# T01_Synth_Glove_v4.net
KiCad netlist of a schematic drawn in EAGLE
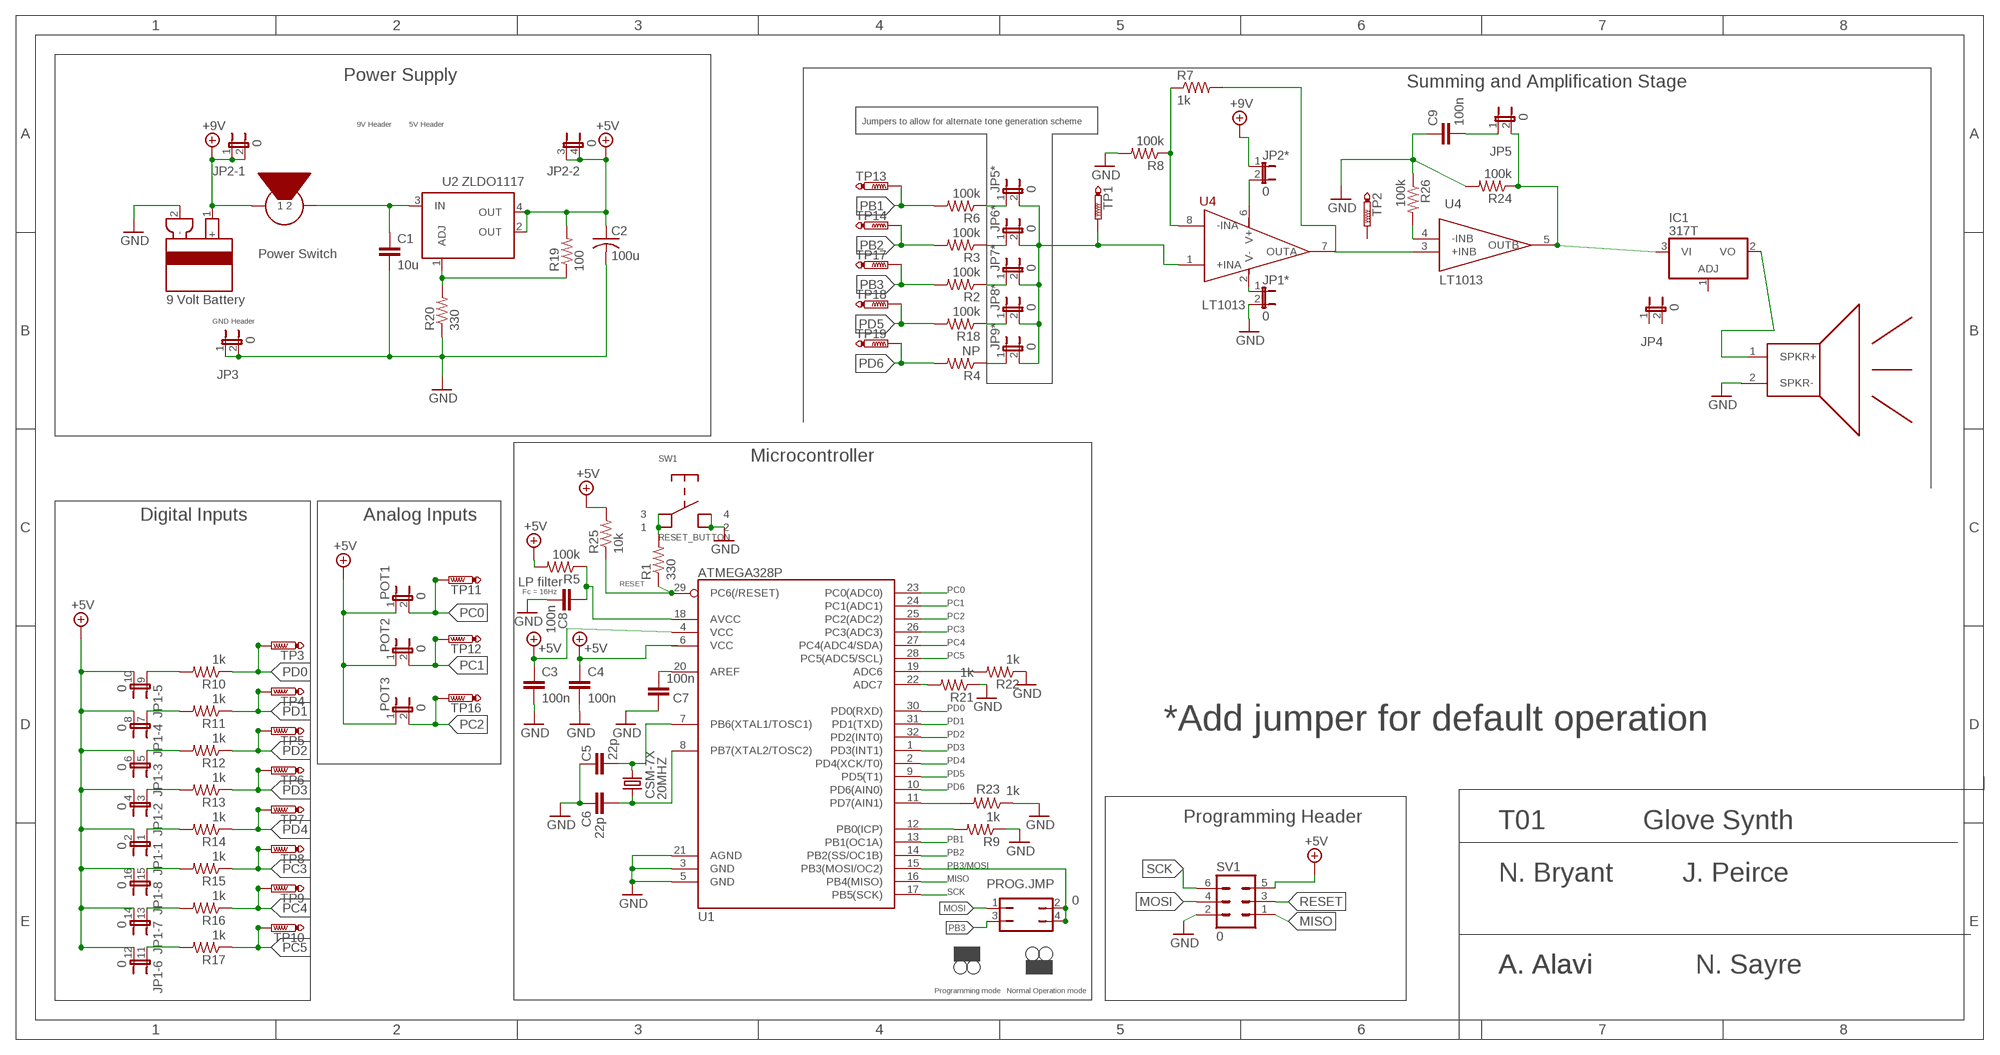
[diagram p0: schematic, sheet 1]

(export (version "E")
  (design (tool "Eeschema 10.0.6"))
  (components
    (comp (ref "20MHZ")
      (value "CSM-7X")
      (footprint "eagle-import:CSM-7X-DU")
      (libsource (lib "eagle-import") (part "CSM-7X-DU"))
    )
    (comp (ref "C1")
      (value "10u")
      (footprint "eagle-import:0603-CAP")
      (libsource (lib "eagle-import") (part "CAP0603-CAP"))
    )
    (comp (ref "C2")
      (value "100u")
      (footprint "eagle-import:C075-042X103")
      (libsource (lib "eagle-import") (part "C-US075-042X103"))
    )
    (comp (ref "C3")
      (value "100n")
      (footprint "eagle-import:0603-CAP")
      (libsource (lib "eagle-import") (part "CAP0603-CAP"))
    )
    (comp (ref "C4")
      (value "100n")
      (footprint "eagle-import:0603-CAP")
      (libsource (lib "eagle-import") (part "CAP0603-CAP"))
    )
    (comp (ref "C5")
      (value "22p")
      (footprint "eagle-import:0603-CAP")
      (libsource (lib "eagle-import") (part "CAP0603-CAP"))
    )
    (comp (ref "C6")
      (value "22p")
      (footprint "eagle-import:0603-CAP")
      (libsource (lib "eagle-import") (part "CAP0603-CAP"))
    )
    (comp (ref "C7")
      (value "100n")
      (footprint "eagle-import:0603-CAP")
      (libsource (lib "eagle-import") (part "CAP0603-CAP"))
    )
    (comp (ref "C8")
      (value "100n")
      (footprint "eagle-import:0603-CAP")
      (libsource (lib "eagle-import") (part "CAP0603-CAP"))
    )
    (comp (ref "C9")
      (value "100n")
      (footprint "eagle-import:0603-CAP")
      (libsource (lib "eagle-import") (part "CAP0603-CAP"))
    )
    (comp (ref "IC1")
      (value "317T")
      (footprint "eagle-import:TO220H")
      (libsource (lib "eagle-import") (part "317T"))
    )
    (comp (ref "JP1")
      (value "0")
      (footprint "eagle-import:JP8Q")
      (libsource (lib "eagle-import") (part "JP8QE"))
    )
    (comp (ref "JP1*")
      (value "0")
      (footprint "eagle-import:JP1")
      (libsource (lib "eagle-import") (part "JP1E"))
    )
    (comp (ref "JP2")
      (value "0")
      (footprint "eagle-import:JP2Q")
      (libsource (lib "eagle-import") (part "JP2QE"))
    )
    (comp (ref "JP2*")
      (value "0")
      (footprint "eagle-import:JP1")
      (libsource (lib "eagle-import") (part "JP1E"))
    )
    (comp (ref "JP3")
      (value "0")
      (footprint "eagle-import:JP1")
      (libsource (lib "eagle-import") (part "JP1E"))
    )
    (comp (ref "JP4")
      (value "0")
      (footprint "eagle-import:JP1")
      (libsource (lib "eagle-import") (part "JP1E"))
    )
    (comp (ref "JP5")
      (value "0")
      (footprint "eagle-import:JP1")
      (libsource (lib "eagle-import") (part "JP1E"))
    )
    (comp (ref "JP5*")
      (value "0")
      (footprint "eagle-import:JP1")
      (libsource (lib "eagle-import") (part "JP1E"))
    )
    (comp (ref "JP6*")
      (value "0")
      (footprint "eagle-import:JP1")
      (libsource (lib "eagle-import") (part "JP1E"))
    )
    (comp (ref "JP7*")
      (value "0")
      (footprint "eagle-import:JP1")
      (libsource (lib "eagle-import") (part "JP1E"))
    )
    (comp (ref "JP8*")
      (value "0")
      (footprint "eagle-import:JP1")
      (libsource (lib "eagle-import") (part "JP1E"))
    )
    (comp (ref "JP9*")
      (value "0")
      (footprint "eagle-import:JP1")
      (libsource (lib "eagle-import") (part "JP1E"))
    )
    (comp (ref "POT1")
      (value "0")
      (footprint "eagle-import:JP1")
      (libsource (lib "eagle-import") (part "JP1E"))
    )
    (comp (ref "POT2")
      (value "0")
      (footprint "eagle-import:JP1")
      (libsource (lib "eagle-import") (part "JP1E"))
    )
    (comp (ref "POT3")
      (value "0")
      (footprint "eagle-import:JP1")
      (libsource (lib "eagle-import") (part "JP1E"))
    )
    (comp (ref "PROG.JMP")
      (value "0")
      (footprint "eagle-import:JP2Q")
      (libsource (lib "eagle-import") (part "JP2Q"))
    )
    (comp (ref "R1")
      (value "330")
      (footprint "eagle-import:0603-RES")
      (libsource (lib "eagle-import") (part "RESISTOR0603"))
    )
    (comp (ref "R2")
      (value "100k")
      (footprint "eagle-import:0603-RES")
      (libsource (lib "eagle-import") (part "RESISTOR0603"))
    )
    (comp (ref "R3")
      (value "100k")
      (footprint "eagle-import:0603-RES")
      (libsource (lib "eagle-import") (part "RESISTOR0603"))
    )
    (comp (ref "R4")
      (value "NP")
      (footprint "eagle-import:0603-RES")
      (libsource (lib "eagle-import") (part "RESISTOR0603"))
    )
    (comp (ref "R5")
      (value "100k")
      (footprint "eagle-import:0603-RES")
      (libsource (lib "eagle-import") (part "RESISTOR0603"))
    )
    (comp (ref "R6")
      (value "100k")
      (footprint "eagle-import:0603-RES")
      (libsource (lib "eagle-import") (part "RESISTOR0603"))
    )
    (comp (ref "R7")
      (value "1k")
      (footprint "eagle-import:0603-RES")
      (libsource (lib "eagle-import") (part "RESISTOR0603"))
    )
    (comp (ref "R8")
      (value "100k")
      (footprint "eagle-import:0603-RES")
      (libsource (lib "eagle-import") (part "RESISTOR0603"))
    )
    (comp (ref "R9")
      (value "1k")
      (footprint "eagle-import:0603-RES")
      (libsource (lib "eagle-import") (part "RESISTOR0603"))
    )
    (comp (ref "R10")
      (value "1k")
      (footprint "eagle-import:0603-RES")
      (libsource (lib "eagle-import") (part "RESISTOR0603"))
    )
    (comp (ref "R11")
      (value "1k")
      (footprint "eagle-import:0603-RES")
      (libsource (lib "eagle-import") (part "RESISTOR0603"))
    )
    (comp (ref "R12")
      (value "1k")
      (footprint "eagle-import:0603-RES")
      (libsource (lib "eagle-import") (part "RESISTOR0603"))
    )
    (comp (ref "R13")
      (value "1k")
      (footprint "eagle-import:0603-RES")
      (libsource (lib "eagle-import") (part "RESISTOR0603"))
    )
    (comp (ref "R14")
      (value "1k")
      (footprint "eagle-import:0603-RES")
      (libsource (lib "eagle-import") (part "RESISTOR0603"))
    )
    (comp (ref "R15")
      (value "1k")
      (footprint "eagle-import:0603-RES")
      (libsource (lib "eagle-import") (part "RESISTOR0603"))
    )
    (comp (ref "R16")
      (value "1k")
      (footprint "eagle-import:0603-RES")
      (libsource (lib "eagle-import") (part "RESISTOR0603"))
    )
    (comp (ref "R17")
      (value "1k")
      (footprint "eagle-import:0603-RES")
      (libsource (lib "eagle-import") (part "RESISTOR0603"))
    )
    (comp (ref "R18")
      (value "100k")
      (footprint "eagle-import:0603-RES")
      (libsource (lib "eagle-import") (part "RESISTOR0603"))
    )
    (comp (ref "R19")
      (value "100")
      (footprint "eagle-import:0603-RES")
      (libsource (lib "eagle-import") (part "RESISTOR0603"))
    )
    (comp (ref "R20")
      (value "330")
      (footprint "eagle-import:0603-RES")
      (libsource (lib "eagle-import") (part "RESISTOR0603"))
    )
    (comp (ref "R21")
      (value "1k")
      (footprint "eagle-import:0603-RES")
      (libsource (lib "eagle-import") (part "RESISTOR0603"))
    )
    (comp (ref "R22")
      (value "1k")
      (footprint "eagle-import:0603-RES")
      (libsource (lib "eagle-import") (part "RESISTOR0603"))
    )
    (comp (ref "R23")
      (value "1k")
      (footprint "eagle-import:0603-RES")
      (libsource (lib "eagle-import") (part "RESISTOR0603"))
    )
    (comp (ref "R24")
      (value "100k")
      (footprint "eagle-import:0603-RES")
      (libsource (lib "eagle-import") (part "RESISTOR0603"))
    )
    (comp (ref "R25")
      (value "10k")
      (footprint "eagle-import:0603-RES")
      (libsource (lib "eagle-import") (part "RESISTOR0603"))
    )
    (comp (ref "R26")
      (value "100k")
      (footprint "eagle-import:0603-RES")
      (libsource (lib "eagle-import") (part "RESISTOR0603"))
    )
    (comp (ref "SV1")
      (value "0")
      (footprint "eagle-import:MA03-2")
      (libsource (lib "eagle-import") (part "MA03-2"))
    )
    (comp (ref "SW1")
      (value "RESET_BUTTON")
      (footprint "eagle-import:RESET_BUTTON")
      (libsource (lib "eagle-import") (part "RESET_BUTTON"))
    )
    (comp (ref "TP1")
      (value "PTR1B2,54")
      (footprint "eagle-import:B2,54")
      (libsource (lib "eagle-import") (part "PTR1B2,54"))
    )
    (comp (ref "TP2")
      (value "PTR1B2,54")
      (footprint "eagle-import:B2,54")
      (libsource (lib "eagle-import") (part "PTR1B2,54"))
    )
    (comp (ref "TP3")
      (value "PTR1B2,54")
      (footprint "eagle-import:B2,54")
      (libsource (lib "eagle-import") (part "PTR1B2,54"))
    )
    (comp (ref "TP4")
      (value "PTR1B2,54")
      (footprint "eagle-import:B2,54")
      (libsource (lib "eagle-import") (part "PTR1B2,54"))
    )
    (comp (ref "TP5")
      (value "PTR1B2,54")
      (footprint "eagle-import:B2,54")
      (libsource (lib "eagle-import") (part "PTR1B2,54"))
    )
    (comp (ref "TP6")
      (value "PTR1B2,54")
      (footprint "eagle-import:B2,54")
      (libsource (lib "eagle-import") (part "PTR1B2,54"))
    )
    (comp (ref "TP7")
      (value "PTR1B2,54")
      (footprint "eagle-import:B2,54")
      (libsource (lib "eagle-import") (part "PTR1B2,54"))
    )
    (comp (ref "TP8")
      (value "PTR1B2,54")
      (footprint "eagle-import:B2,54")
      (libsource (lib "eagle-import") (part "PTR1B2,54"))
    )
    (comp (ref "TP9")
      (value "PTR1B2,54")
      (footprint "eagle-import:B2,54")
      (libsource (lib "eagle-import") (part "PTR1B2,54"))
    )
    (comp (ref "TP10")
      (value "PTR1B2,54")
      (footprint "eagle-import:B2,54")
      (libsource (lib "eagle-import") (part "PTR1B2,54"))
    )
    (comp (ref "TP11")
      (value "PTR1B2,54")
      (footprint "eagle-import:B2,54")
      (libsource (lib "eagle-import") (part "PTR1B2,54"))
    )
    (comp (ref "TP12")
      (value "PTR1B2,54")
      (footprint "eagle-import:B2,54")
      (libsource (lib "eagle-import") (part "PTR1B2,54"))
    )
    (comp (ref "TP13")
      (value "PTR1B2,54")
      (footprint "eagle-import:B2,54")
      (libsource (lib "eagle-import") (part "PTR1B2,54"))
    )
    (comp (ref "TP14")
      (value "PTR1B2,54")
      (footprint "eagle-import:B2,54")
      (libsource (lib "eagle-import") (part "PTR1B2,54"))
    )
    (comp (ref "TP16")
      (value "PTR1B2,54")
      (footprint "eagle-import:B2,54")
      (libsource (lib "eagle-import") (part "PTR1B2,54"))
    )
    (comp (ref "TP17")
      (value "PTR1B2,54")
      (footprint "eagle-import:B2,54")
      (libsource (lib "eagle-import") (part "PTR1B2,54"))
    )
    (comp (ref "TP18")
      (value "PTR1B2,54")
      (footprint "eagle-import:B2,54")
      (libsource (lib "eagle-import") (part "PTR1B2,54"))
    )
    (comp (ref "TP19")
      (value "PTR1B2,54")
      (footprint "eagle-import:B2,54")
      (libsource (lib "eagle-import") (part "PTR1B2,54"))
    )
    (comp (ref "U$1")
      (value "SPEAKER")
      (footprint "eagle-import:JP1")
      (libsource (lib "eagle-import") (part "SPEAKER"))
    )
    (comp (ref "U$7")
      (value "POWER_SWITCH")
      (footprint "eagle-import:JP1")
      (libsource (lib "eagle-import") (part "POWER_SWITCH"))
    )
    (comp (ref "U$8")
      (value "9VOLTBATTERY")
      (footprint "eagle-import:JP1")
      (libsource (lib "eagle-import") (part "9VOLTBATTERY"))
    )
    (comp (ref "U1")
      (value "ATMEGA328P")
      (footprint "eagle-import:TQFP32-08")
      (libsource (lib "eagle-import") (part "ATMEGA328_SMT"))
    )
    (comp (ref "U2")
      (value "ZLDO1117")
      (footprint "eagle-import:SOT223")
      (libsource (lib "eagle-import") (part "ZLDO1117"))
    )
    (comp (ref "U4")
      (value "LT1013")
      (footprint "eagle-import:SO08")
      (libsource (lib "eagle-import") (part "LT1013"))
    )
  )
  (nets
    (net (code "1") (name "+5V") (class "Default")
      (node (ref "C2") (pin "1") (pinfunction "1_1") (pintype "passive"))
      (node (ref "C3") (pin "1") (pinfunction "1_1") (pintype "passive"))
      (node (ref "C4") (pin "1") (pinfunction "1_1") (pintype "passive"))
      (node (ref "JP1") (pin "10") (pinfunction "2_10") (pintype "passive"))
      (node (ref "JP1") (pin "12") (pinfunction "2_12") (pintype "passive"))
      (node (ref "JP1") (pin "14") (pinfunction "2_14") (pintype "passive"))
      (node (ref "JP1") (pin "16") (pinfunction "2_16") (pintype "passive"))
      (node (ref "JP1") (pin "2") (pinfunction "2_2") (pintype "passive"))
      (node (ref "JP1") (pin "4") (pinfunction "2_4") (pintype "passive"))
      (node (ref "JP1") (pin "6") (pinfunction "2_6") (pintype "passive"))
      (node (ref "JP1") (pin "8") (pinfunction "2_8") (pintype "passive"))
      (node (ref "JP2") (pin "3") (pinfunction "1_3") (pintype "passive"))
      (node (ref "JP2") (pin "4") (pinfunction "2_4") (pintype "passive"))
      (node (ref "POT1") (pin "1") (pinfunction "1_1") (pintype "passive"))
      (node (ref "POT2") (pin "1") (pinfunction "1_1") (pintype "passive"))
      (node (ref "POT3") (pin "1") (pinfunction "1_1") (pintype "passive"))
      (node (ref "R19") (pin "2") (pinfunction "2_2") (pintype "passive"))
      (node (ref "R25") (pin "2") (pinfunction "2_2") (pintype "passive"))
      (node (ref "R5") (pin "2") (pinfunction "2_2") (pintype "passive"))
      (node (ref "SV1") (pin "5") (pinfunction "5_5") (pintype "passive"))
      (node (ref "U1") (pin "4") (pinfunction "VCC_4") (pintype "bidirectional"))
      (node (ref "U2") (pin "2") (pinfunction "OUT_2") (pintype "bidirectional"))
      (node (ref "U2") (pin "4") (pinfunction "OUT_4") (pintype "bidirectional"))
    )
    (net (code "2") (name "+9V") (class "Default")
      (node (ref "JP2") (pin "1") (pinfunction "1_1") (pintype "passive"))
      (node (ref "JP2") (pin "2") (pinfunction "2_2") (pintype "passive"))
      (node (ref "JP2*") (pin "1") (pinfunction "1_1") (pintype "passive"))
      (node (ref "U$7") (pin "1") (pinfunction "1_1") (pintype "bidirectional"))
      (node (ref "U$8") (pin "1") (pinfunction "+_1") (pintype "bidirectional"))
    )
    (net (code "3") (name "/PB3{slash}MOSI") (class "Default")
      (node (ref "PROG.JMP") (pin "2") (pinfunction "2_2") (pintype "passive"))
      (node (ref "PROG.JMP") (pin "4") (pinfunction "4_4") (pintype "passive"))
      (node (ref "U1") (pin "15") (pinfunction "PB3(MOSI/OC2)_15") (pintype "bidirectional"))
    )
    (net (code "4") (name "GND") (class "Default")
      (node (ref "C1") (pin "2") (pinfunction "2_2") (pintype "passive"))
      (node (ref "C2") (pin "2") (pinfunction "2_2") (pintype "passive"))
      (node (ref "C3") (pin "2") (pinfunction "2_2") (pintype "passive"))
      (node (ref "C4") (pin "2") (pinfunction "2_2") (pintype "passive"))
      (node (ref "C5") (pin "2") (pinfunction "2_2") (pintype "passive"))
      (node (ref "C6") (pin "2") (pinfunction "2_2") (pintype "passive"))
      (node (ref "C7") (pin "2") (pinfunction "2_2") (pintype "passive"))
      (node (ref "C8") (pin "2") (pinfunction "2_2") (pintype "passive"))
      (node (ref "C9") (pin "1") (pinfunction "1_1") (pintype "passive"))
      (node (ref "JP1*") (pin "2") (pinfunction "2_2") (pintype "passive"))
      (node (ref "JP3") (pin "1") (pinfunction "1_1") (pintype "passive"))
      (node (ref "JP3") (pin "2") (pinfunction "2_2") (pintype "passive"))
      (node (ref "R20") (pin "1") (pinfunction "1_1") (pintype "passive"))
      (node (ref "R21") (pin "1") (pinfunction "1_1") (pintype "passive"))
      (node (ref "R22") (pin "1") (pinfunction "1_1") (pintype "passive"))
      (node (ref "R23") (pin "1") (pinfunction "1_1") (pintype "passive"))
      (node (ref "R24") (pin "2") (pinfunction "2_2") (pintype "passive"))
      (node (ref "R26") (pin "1") (pinfunction "1_1") (pintype "passive"))
      (node (ref "R8") (pin "2") (pinfunction "2_2") (pintype "passive"))
      (node (ref "R9") (pin "1") (pinfunction "1_1") (pintype "passive"))
      (node (ref "SV1") (pin "2") (pinfunction "2_2") (pintype "passive"))
      (node (ref "SW1") (pin "2") (pinfunction "2_2") (pintype "bidirectional"))
      (node (ref "SW1") (pin "4") (pinfunction "4_4") (pintype "bidirectional"))
      (node (ref "U$1") (pin "2") (pinfunction "SPKR-_2") (pintype "bidirectional"))
      (node (ref "U$8") (pin "2") (pinfunction "-_2") (pintype "bidirectional"))
      (node (ref "U1") (pin "21") (pinfunction "AGND_21") (pintype "bidirectional"))
      (node (ref "U1") (pin "3") (pinfunction "GND_3") (pintype "bidirectional"))
      (node (ref "U1") (pin "5") (pinfunction "GND_5") (pintype "bidirectional"))
    )
    (net (code "5") (name "MISO") (class "Default")
      (node (ref "SV1") (pin "1") (pinfunction "1_1") (pintype "passive"))
      (node (ref "U1") (pin "16") (pinfunction "PB4(MISO)_16") (pintype "bidirectional"))
    )
    (net (code "6") (name "MOSI") (class "Default")
      (node (ref "PROG.JMP") (pin "1") (pinfunction "1_1") (pintype "passive"))
      (node (ref "SV1") (pin "4") (pinfunction "4_4") (pintype "passive"))
    )
    (net (code "7") (name "Net-(C9-Pad2)") (class "Default")
      (node (ref "C9") (pin "2") (pinfunction "2_2") (pintype "passive"))
      (node (ref "JP5") (pin "1") (pinfunction "1_1") (pintype "passive"))
    )
    (net (code "8") (name "Net-(IC1-VI)") (class "Default")
      (node (ref "IC1") (pin "3") (pinfunction "VI_3") (pintype "input"))
      (node (ref "JP5") (pin "2") (pinfunction "2_2") (pintype "passive"))
      (node (ref "R24") (pin "1") (pinfunction "1_1") (pintype "passive"))
      (node (ref "U4") (pin "5") (pinfunction "OUTB_5") (pintype "bidirectional"))
    )
    (net (code "9") (name "Net-(JP1-Pad1)") (class "Default")
      (node (ref "JP1") (pin "1") (pinfunction "1_1") (pintype "passive"))
      (node (ref "R14") (pin "2") (pinfunction "2_2") (pintype "passive"))
    )
    (net (code "10") (name "Net-(JP1B-1)") (class "Default")
      (node (ref "JP1") (pin "3") (pinfunction "1_3") (pintype "passive"))
      (node (ref "R13") (pin "2") (pinfunction "2_2") (pintype "passive"))
    )
    (net (code "11") (name "Net-(JP1C-1)") (class "Default")
      (node (ref "JP1") (pin "5") (pinfunction "1_5") (pintype "passive"))
      (node (ref "R12") (pin "2") (pinfunction "2_2") (pintype "passive"))
    )
    (net (code "12") (name "Net-(JP1D-1)") (class "Default")
      (node (ref "JP1") (pin "7") (pinfunction "1_7") (pintype "passive"))
      (node (ref "R11") (pin "2") (pinfunction "2_2") (pintype "passive"))
    )
    (net (code "13") (name "Net-(JP1E-1)") (class "Default")
      (node (ref "JP1") (pin "9") (pinfunction "1_9") (pintype "passive"))
      (node (ref "R10") (pin "2") (pinfunction "2_2") (pintype "passive"))
    )
    (net (code "14") (name "Net-(JP1F-1)") (class "Default")
      (node (ref "JP1") (pin "11") (pinfunction "1_11") (pintype "passive"))
      (node (ref "R17") (pin "2") (pinfunction "2_2") (pintype "passive"))
    )
    (net (code "15") (name "Net-(JP1G-1)") (class "Default")
      (node (ref "JP1") (pin "13") (pinfunction "1_13") (pintype "passive"))
      (node (ref "R16") (pin "2") (pinfunction "2_2") (pintype "passive"))
    )
    (net (code "16") (name "Net-(JP1H-1)") (class "Default")
      (node (ref "JP1") (pin "15") (pinfunction "1_15") (pintype "passive"))
      (node (ref "R15") (pin "2") (pinfunction "2_2") (pintype "passive"))
    )
    (net (code "17") (name "Net-(JP5*-Pad1)") (class "Default")
      (node (ref "JP5*") (pin "1") (pinfunction "1_1") (pintype "passive"))
      (node (ref "R6") (pin "1") (pinfunction "1_1") (pintype "passive"))
    )
    (net (code "18") (name "Net-(JP6*-Pad1)") (class "Default")
      (node (ref "JP6*") (pin "1") (pinfunction "1_1") (pintype "passive"))
      (node (ref "R3") (pin "1") (pinfunction "1_1") (pintype "passive"))
    )
    (net (code "19") (name "Net-(JP7*-Pad1)") (class "Default")
      (node (ref "JP7*") (pin "1") (pinfunction "1_1") (pintype "passive"))
      (node (ref "R2") (pin "1") (pinfunction "1_1") (pintype "passive"))
    )
    (net (code "20") (name "Net-(JP8*-Pad1)") (class "Default")
      (node (ref "JP8*") (pin "1") (pinfunction "1_1") (pintype "passive"))
      (node (ref "R18") (pin "1") (pinfunction "1_1") (pintype "passive"))
    )
    (net (code "21") (name "Net-(JP9*-Pad1)") (class "Default")
      (node (ref "JP9*") (pin "1") (pinfunction "1_1") (pintype "passive"))
      (node (ref "R4") (pin "1") (pinfunction "1_1") (pintype "passive"))
    )
    (net (code "22") (name "Net-(R1-Pad2)") (class "Default")
      (node (ref "R1") (pin "2") (pinfunction "2_2") (pintype "passive"))
      (node (ref "SW1") (pin "1") (pinfunction "1_1") (pintype "bidirectional"))
      (node (ref "SW1") (pin "3") (pinfunction "3_3") (pintype "bidirectional"))
    )
    (net (code "23") (name "Net-(U1-ADC6)") (class "Default")
      (node (ref "R22") (pin "2") (pinfunction "2_2") (pintype "passive"))
      (node (ref "U1") (pin "19") (pinfunction "ADC6_19") (pintype "bidirectional"))
    )
    (net (code "24") (name "Net-(U1-ADC7)") (class "Default")
      (node (ref "R21") (pin "2") (pinfunction "2_2") (pintype "passive"))
      (node (ref "U1") (pin "22") (pinfunction "ADC7_22") (pintype "bidirectional"))
    )
    (net (code "25") (name "Net-(U1-AREF)") (class "Default")
      (node (ref "C7") (pin "1") (pinfunction "1_1") (pintype "passive"))
      (node (ref "U1") (pin "20") (pinfunction "AREF_20") (pintype "bidirectional"))
    )
    (net (code "26") (name "Net-(U1-AVCC)") (class "Default")
      (node (ref "C8") (pin "1") (pinfunction "1_1") (pintype "passive"))
      (node (ref "R5") (pin "1") (pinfunction "1_1") (pintype "passive"))
      (node (ref "U1") (pin "18") (pinfunction "AVCC_18") (pintype "bidirectional"))
    )
    (net (code "27") (name "Net-(U1-PB0(ICP))") (class "Default")
      (node (ref "R9") (pin "2") (pinfunction "2_2") (pintype "passive"))
      (node (ref "U1") (pin "12") (pinfunction "PB0(ICP)_12") (pintype "bidirectional"))
    )
    (net (code "28") (name "Net-(U1-PB6(XTAL1{slash}TOSC1))") (class "Default")
      (node (ref "20MHZ") (pin "1") (pinfunction "1_1") (pintype "passive"))
      (node (ref "C5") (pin "1") (pinfunction "1_1") (pintype "passive"))
      (node (ref "U1") (pin "7") (pinfunction "PB6(XTAL1/TOSC1)_7") (pintype "bidirectional"))
    )
    (net (code "29") (name "Net-(U1-PB7(XTAL2{slash}TOSC2))") (class "Default")
      (node (ref "20MHZ") (pin "2") (pinfunction "2_2") (pintype "passive"))
      (node (ref "C6") (pin "1") (pinfunction "1_1") (pintype "passive"))
      (node (ref "U1") (pin "8") (pinfunction "PB7(XTAL2/TOSC2)_8") (pintype "bidirectional"))
    )
    (net (code "30") (name "Net-(U1-PD7(AIN1))") (class "Default")
      (node (ref "R23") (pin "2") (pinfunction "2_2") (pintype "passive"))
      (node (ref "U1") (pin "11") (pinfunction "PD7(AIN1)_11") (pintype "bidirectional"))
    )
    (net (code "31") (name "Net-(U2-ADJ)") (class "Default")
      (node (ref "R19") (pin "1") (pinfunction "1_1") (pintype "passive"))
      (node (ref "R20") (pin "2") (pinfunction "2_2") (pintype "passive"))
      (node (ref "U2") (pin "1") (pinfunction "ADJ_1") (pintype "bidirectional"))
    )
    (net (code "32") (name "Net-(U2-IN)") (class "Default")
      (node (ref "C1") (pin "1") (pinfunction "1_1") (pintype "passive"))
      (node (ref "U$7") (pin "2") (pinfunction "2_2") (pintype "bidirectional"))
      (node (ref "U2") (pin "3") (pinfunction "IN_3") (pintype "bidirectional"))
    )
    (net (code "33") (name "Net-(U4-+INA)") (class "Default")
      (node (ref "JP5*") (pin "2") (pinfunction "2_2") (pintype "passive"))
      (node (ref "JP6*") (pin "2") (pinfunction "2_2") (pintype "passive"))
      (node (ref "JP7*") (pin "2") (pinfunction "2_2") (pintype "passive"))
      (node (ref "JP8*") (pin "2") (pinfunction "2_2") (pintype "passive"))
      (node (ref "JP9*") (pin "2") (pinfunction "2_2") (pintype "passive"))
      (node (ref "TP1") (pin "TP") (pinfunction "TP_TP") (pintype "input"))
      (node (ref "U4") (pin "1") (pinfunction "+INA_1") (pintype "bidirectional"))
    )
    (net (code "34") (name "Net-(U4--INA)") (class "Default")
      (node (ref "R7") (pin "1") (pinfunction "1_1") (pintype "passive"))
      (node (ref "R8") (pin "1") (pinfunction "1_1") (pintype "passive"))
      (node (ref "U4") (pin "8") (pinfunction "-INA_8") (pintype "bidirectional"))
    )
    (net (code "35") (name "Net-(U4--INB)") (class "Default")
      (node (ref "R26") (pin "2") (pinfunction "2_2") (pintype "passive"))
      (node (ref "U4") (pin "4") (pinfunction "-INB_4") (pintype "bidirectional"))
    )
    (net (code "36") (name "Net-(U4-OUTA)") (class "Default")
      (node (ref "R7") (pin "2") (pinfunction "2_2") (pintype "passive"))
      (node (ref "U4") (pin "7") (pinfunction "OUTA_7") (pintype "bidirectional"))
    )
    (net (code "37") (name "Net-(U4-V+)") (class "Default")
      (node (ref "JP2*") (pin "2") (pinfunction "2_2") (pintype "passive"))
      (node (ref "U4") (pin "6") (pinfunction "V+_6") (pintype "power_in"))
    )
    (net (code "38") (name "Net-(U4-V-)") (class "Default")
      (node (ref "JP1*") (pin "1") (pinfunction "1_1") (pintype "passive"))
      (node (ref "U4") (pin "2") (pinfunction "V-_2") (pintype "power_in"))
    )
    (net (code "39") (name "PB1") (class "Default")
      (node (ref "R6") (pin "2") (pinfunction "2_2") (pintype "passive"))
      (node (ref "TP13") (pin "TP") (pinfunction "TP_TP") (pintype "input"))
      (node (ref "U1") (pin "13") (pinfunction "PB1(OC1A)_13") (pintype "bidirectional"))
    )
    (net (code "40") (name "PB2") (class "Default")
      (node (ref "R3") (pin "2") (pinfunction "2_2") (pintype "passive"))
      (node (ref "TP14") (pin "TP") (pinfunction "TP_TP") (pintype "input"))
      (node (ref "U1") (pin "14") (pinfunction "PB2(SS/OC1B)_14") (pintype "bidirectional"))
    )
    (net (code "41") (name "PB3") (class "Default")
      (node (ref "PROG.JMP") (pin "3") (pinfunction "3_3") (pintype "passive"))
      (node (ref "R2") (pin "2") (pinfunction "2_2") (pintype "passive"))
      (node (ref "TP17") (pin "TP") (pinfunction "TP_TP") (pintype "input"))
    )
    (net (code "42") (name "PC0") (class "Default")
      (node (ref "POT1") (pin "2") (pinfunction "2_2") (pintype "passive"))
      (node (ref "TP11") (pin "TP") (pinfunction "TP_TP") (pintype "input"))
      (node (ref "U1") (pin "23") (pinfunction "PC0(ADC0)_23") (pintype "bidirectional"))
    )
    (net (code "43") (name "PC1") (class "Default")
      (node (ref "POT2") (pin "2") (pinfunction "2_2") (pintype "passive"))
      (node (ref "TP12") (pin "TP") (pinfunction "TP_TP") (pintype "input"))
      (node (ref "U1") (pin "24") (pinfunction "PC1(ADC1)_24") (pintype "bidirectional"))
    )
    (net (code "44") (name "PC2") (class "Default")
      (node (ref "POT3") (pin "2") (pinfunction "2_2") (pintype "passive"))
      (node (ref "TP16") (pin "TP") (pinfunction "TP_TP") (pintype "input"))
      (node (ref "U1") (pin "25") (pinfunction "PC2(ADC2)_25") (pintype "bidirectional"))
    )
    (net (code "45") (name "PC3") (class "Default")
      (node (ref "R15") (pin "1") (pinfunction "1_1") (pintype "passive"))
      (node (ref "TP8") (pin "TP") (pinfunction "TP_TP") (pintype "input"))
      (node (ref "U1") (pin "26") (pinfunction "PC3(ADC3)_26") (pintype "bidirectional"))
    )
    (net (code "46") (name "PC4") (class "Default")
      (node (ref "R16") (pin "1") (pinfunction "1_1") (pintype "passive"))
      (node (ref "TP9") (pin "TP") (pinfunction "TP_TP") (pintype "input"))
      (node (ref "U1") (pin "27") (pinfunction "PC4(ADC4/SDA)_27") (pintype "bidirectional"))
    )
    (net (code "47") (name "PC5") (class "Default")
      (node (ref "R17") (pin "1") (pinfunction "1_1") (pintype "passive"))
      (node (ref "TP10") (pin "TP") (pinfunction "TP_TP") (pintype "input"))
      (node (ref "U1") (pin "28") (pinfunction "PC5(ADC5/SCL)_28") (pintype "bidirectional"))
    )
    (net (code "48") (name "PD0") (class "Default")
      (node (ref "R10") (pin "1") (pinfunction "1_1") (pintype "passive"))
      (node (ref "TP3") (pin "TP") (pinfunction "TP_TP") (pintype "input"))
      (node (ref "U1") (pin "30") (pinfunction "PD0(RXD)_30") (pintype "bidirectional"))
    )
    (net (code "49") (name "PD1") (class "Default")
      (node (ref "R11") (pin "1") (pinfunction "1_1") (pintype "passive"))
      (node (ref "TP4") (pin "TP") (pinfunction "TP_TP") (pintype "input"))
      (node (ref "U1") (pin "31") (pinfunction "PD1(TXD)_31") (pintype "bidirectional"))
    )
    (net (code "50") (name "PD2") (class "Default")
      (node (ref "R12") (pin "1") (pinfunction "1_1") (pintype "passive"))
      (node (ref "TP5") (pin "TP") (pinfunction "TP_TP") (pintype "input"))
      (node (ref "U1") (pin "32") (pinfunction "PD2(INT0)_32") (pintype "bidirectional"))
    )
    (net (code "51") (name "PD3") (class "Default")
      (node (ref "R13") (pin "1") (pinfunction "1_1") (pintype "passive"))
      (node (ref "TP6") (pin "TP") (pinfunction "TP_TP") (pintype "input"))
      (node (ref "U1") (pin "1") (pinfunction "PD3(INT1)_1") (pintype "bidirectional"))
    )
    (net (code "52") (name "PD4") (class "Default")
      (node (ref "R14") (pin "1") (pinfunction "1_1") (pintype "passive"))
      (node (ref "TP7") (pin "TP") (pinfunction "TP_TP") (pintype "input"))
      (node (ref "U1") (pin "2") (pinfunction "PD4(XCK/T0)_2") (pintype "bidirectional"))
    )
    (net (code "53") (name "PD5") (class "Default")
      (node (ref "R18") (pin "2") (pinfunction "2_2") (pintype "passive"))
      (node (ref "TP18") (pin "TP") (pinfunction "TP_TP") (pintype "input"))
      (node (ref "U1") (pin "9") (pinfunction "PD5(T1)_9") (pintype "bidirectional"))
    )
    (net (code "54") (name "PD6") (class "Default")
      (node (ref "R4") (pin "2") (pinfunction "2_2") (pintype "passive"))
      (node (ref "TP19") (pin "TP") (pinfunction "TP_TP") (pintype "input"))
      (node (ref "U1") (pin "10") (pinfunction "PD6(AIN0)_10") (pintype "bidirectional"))
    )
    (net (code "55") (name "RESET") (class "Default")
      (node (ref "R1") (pin "1") (pinfunction "1_1") (pintype "passive"))
      (node (ref "R25") (pin "1") (pinfunction "1_1") (pintype "passive"))
      (node (ref "SV1") (pin "3") (pinfunction "3_3") (pintype "passive"))
      (node (ref "U1") (pin "29") (pinfunction "PC6(/RESET)_29") (pintype "bidirectional"))
    )
    (net (code "56") (name "SCK") (class "Default")
      (node (ref "SV1") (pin "6") (pinfunction "6_6") (pintype "passive"))
      (node (ref "U1") (pin "17") (pinfunction "PB5(SCK)_17") (pintype "bidirectional"))
    )
    (net (code "57") (name "unconnected-(IC1-ADJ-Pad1)") (class "Default")
      (node (ref "IC1") (pin "1") (pinfunction "ADJ_1") (pintype "input"))
    )
    (net (code "58") (name "unconnected-(IC1-VO-Pad2)") (class "Default")
      (node (ref "IC1") (pin "2") (pinfunction "VO_2") (pintype "passive"))
    )
    (net (code "59") (name "unconnected-(JP4-Pad1)") (class "Default")
      (node (ref "JP4") (pin "1") (pinfunction "1_1") (pintype "passive"))
    )
    (net (code "60") (name "unconnected-(JP4-Pad2)") (class "Default")
      (node (ref "JP4") (pin "2") (pinfunction "2_2") (pintype "passive"))
    )
    (net (code "61") (name "unconnected-(TP2-PadTP)") (class "Default")
      (node (ref "TP2") (pin "TP") (pinfunction "TP_TP") (pintype "input"))
    )
    (net (code "62") (name "unconnected-(U$1-SPKR+-Pad1)") (class "Default")
      (node (ref "U$1") (pin "1") (pinfunction "SPKR+_1") (pintype "bidirectional"))
    )
    (net (code "63") (name "unconnected-(U1-VCC-Pad6)") (class "Default")
      (node (ref "U1") (pin "6") (pinfunction "VCC_6") (pintype "bidirectional"))
    )
    (net (code "64") (name "unconnected-(U4-+INB-Pad3)") (class "Default")
      (node (ref "U4") (pin "3") (pinfunction "+INB_3") (pintype "bidirectional"))
    )
  )
)
